# 2021-06-02.net
KiCad netlist of a schematic drawn in Altium Designer
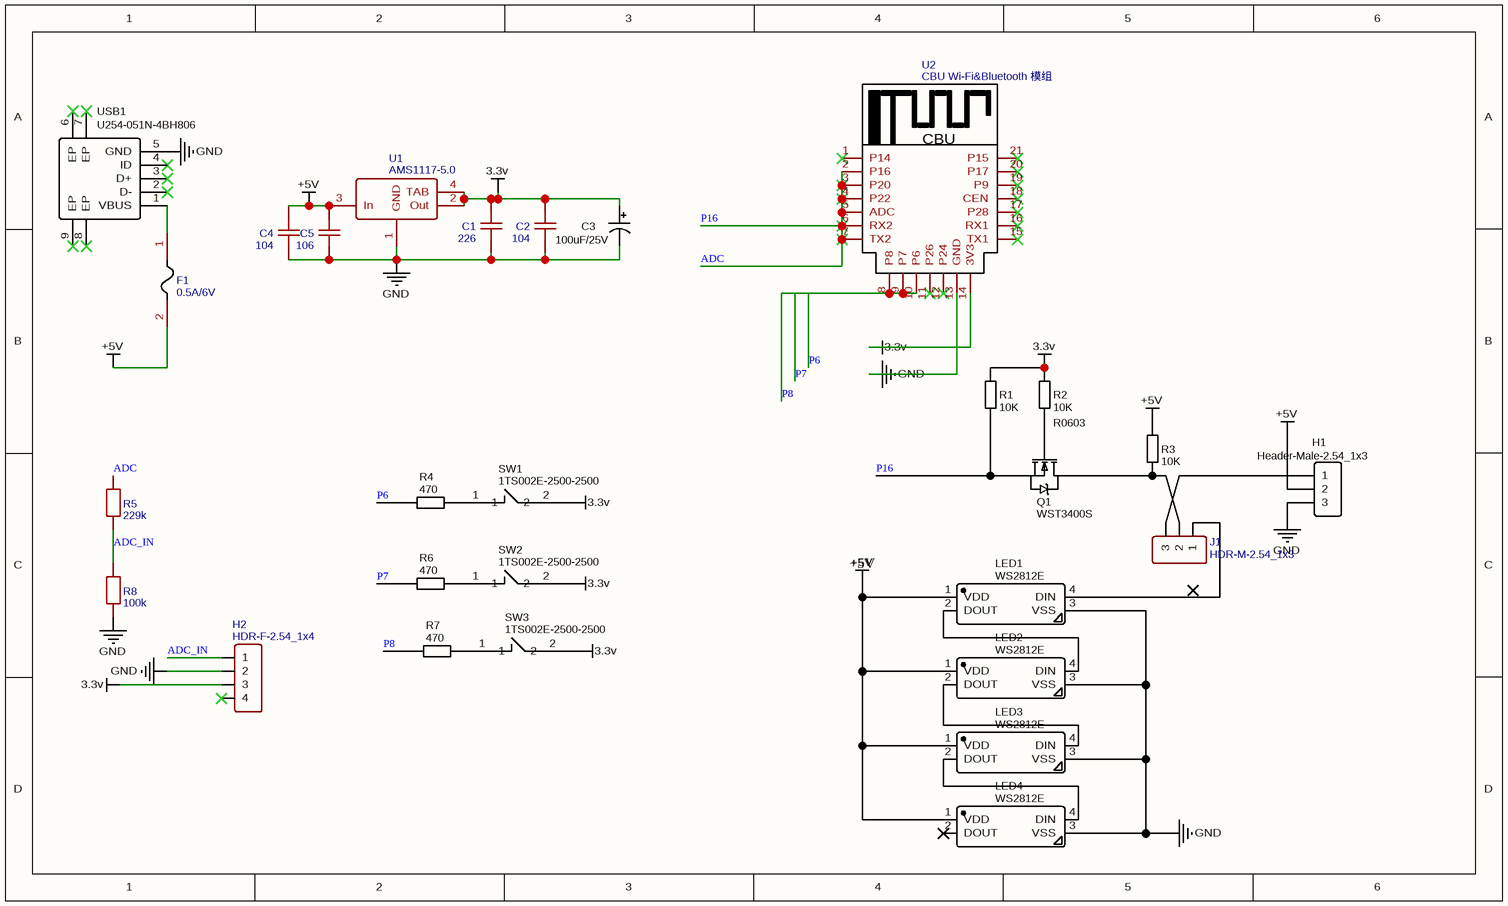
[diagram p0: 原理图_2021-06-02.schdoc]

(export (version "E")
  (design (tool "Eeschema 10.0.6"))
  (components
    (comp (ref "C1")
      (value "226")
      (fields (field (name "BOM_MANUFACTURER PART") "?"))
      (libsource (lib "altium-import") (part "root_1_226_"))
    )
    (comp (ref "C2")
      (value "104")
      (fields (field (name "BOM_MANUFACTURER PART") "?"))
      (libsource (lib "altium-import") (part "root_1_104_"))
    )
    (comp (ref "C3")
      (value "100uF/25V")
      (fields
        (field (name "BOM_MANUFACTURER PART") "RVT1E101M0607")
        (field (name "BOM_SUPPLIER PART") "C3338")
      )
      (libsource (lib "altium-import") (part "root_0_100uF/25V_"))
    )
    (comp (ref "C4")
      (value "104")
      (fields (field (name "BOM_MANUFACTURER PART") "?"))
      (libsource (lib "altium-import") (part "root_1_104_"))
    )
    (comp (ref "C5")
      (value "106")
      (fields (field (name "BOM_MANUFACTURER PART") "?"))
      (libsource (lib "altium-import") (part "root_1_106_"))
    )
    (comp (ref "F1") (value "0.5A/6V") (libsource (lib "altium-import") (part "root_3_0.5A/6V_")))
    (comp (ref "H1")
      (value "Header-Male-2.54_1x3")
      (fields
        (field (name "BOM_MANUFACTURER PART") "Header2.54mm 1*3P")
        (field (name "BOM_SUPPLIER PART") "C49257")
      )
      (libsource (lib "altium-import") (part "root_0_Header-Male-2.54_1x3_"))
    )
    (comp (ref "H2")
      (value "HDR-F-2.54_1x4")
      (fields (field (name "BOM_SUPPLIER PART") "C225501") (field (name "CONTRIBUTOR") "LCEDA_Lib"))
      (libsource (lib "altium-import") (part "root_0_HDR-F-2.54_1x4_"))
    )
    (comp (ref "J1")
      (value "HDR-M-2.54_1x3")
      (fields (field (name "BOM_SUPPLIER PART") "C180248") (field (name "CONTRIBUTOR") "LCEDA_Lib"))
      (libsource (lib "altium-import") (part "root_3_HDR-M-2.54_1x3_"))
    )
    (comp (ref "LED1")
      (value "WS2812E")
      (fields (field (name "BOM_SUPPLIER PART") "C139127") (field (name "CONTRIBUTOR") "LCSC"))
      (libsource (lib "altium-import") (part "root_0_WS2812E_"))
    )
    (comp (ref "LED2")
      (value "WS2812E")
      (fields (field (name "BOM_SUPPLIER PART") "C139127") (field (name "CONTRIBUTOR") "LCSC"))
      (libsource (lib "altium-import") (part "root_0_WS2812E_"))
    )
    (comp (ref "LED3")
      (value "WS2812E")
      (fields (field (name "BOM_SUPPLIER PART") "C139127") (field (name "CONTRIBUTOR") "LCSC"))
      (libsource (lib "altium-import") (part "root_0_WS2812E_"))
    )
    (comp (ref "LED4")
      (value "WS2812E")
      (fields (field (name "BOM_SUPPLIER PART") "C139127") (field (name "CONTRIBUTOR") "LCSC"))
      (libsource (lib "altium-import") (part "root_0_WS2812E_"))
    )
    (comp (ref "Q1")
      (value "WST3400S")
      (fields (field (name "BOM_SUPPLIER PART") "C105164"))
      (libsource (lib "altium-import") (part "root_3_WST3400S_"))
    )
    (comp (ref "R1")
      (value "10K")
      (fields
        (field (name "BOM_MANUFACTURER PART") "RC0603JR-0710KL")
        (field (name "BOM_SUPPLIER PART") "C99198")
      )
      (libsource (lib "altium-import") (part "root_3_10K_"))
    )
    (comp (ref "R2")
      (value "10K")
      (fields
        (field (name "BOM_MANUFACTURER PART") "RC0603JR-0710KL")
        (field (name "BOM_SUPPLIER PART") "C99198")
      )
      (libsource (lib "altium-import") (part "root_3_10K_"))
    )
    (comp (ref "R3")
      (value "10K")
      (fields
        (field (name "BOM_MANUFACTURER PART") "RC0603JR-0710KL")
        (field (name "BOM_SUPPLIER PART") "C99198")
      )
      (libsource (lib "altium-import") (part "root_3_10K_"))
    )
    (comp (ref "R4")
      (value "470")
      (fields
        (field (name "BOM_MANUFACTURER PART") "0603WAJ0471T5E")
        (field (name "BOM_SUPPLIER PART") "C25241")
      )
      (libsource (lib "altium-import") (part "root_2_470_"))
    )
    (comp (ref "R5")
      (value "229k")
      (fields (field (name "CONTRIBUTOR") "LCEDA_Lib"))
      (libsource (lib "altium-import") (part "root_1_229k_"))
    )
    (comp (ref "R6")
      (value "470")
      (fields
        (field (name "BOM_MANUFACTURER PART") "0603WAJ0471T5E")
        (field (name "BOM_SUPPLIER PART") "C25241")
      )
      (libsource (lib "altium-import") (part "root_2_470_"))
    )
    (comp (ref "R7")
      (value "470")
      (fields
        (field (name "BOM_MANUFACTURER PART") "0603WAJ0471T5E")
        (field (name "BOM_SUPPLIER PART") "C25241")
      )
      (libsource (lib "altium-import") (part "root_2_470_"))
    )
    (comp (ref "R8")
      (value "100k")
      (fields (field (name "CONTRIBUTOR") "LCEDA_Lib"))
      (libsource (lib "altium-import") (part "root_1_100k_"))
    )
    (comp (ref "SW1")
      (value "1TS002E-2500-2500")
      (fields (field (name "BOM_SUPPLIER PART") "C329185") (field (name "CONTRIBUTOR") "LCSC"))
      (libsource (lib "altium-import") (part "root_0_1TS002E-2500-2500_"))
    )
    (comp (ref "SW2")
      (value "1TS002E-2500-2500")
      (fields (field (name "BOM_SUPPLIER PART") "C329185") (field (name "CONTRIBUTOR") "LCSC"))
      (libsource (lib "altium-import") (part "root_0_1TS002E-2500-2500_"))
    )
    (comp (ref "SW3")
      (value "1TS002E-2500-2500")
      (fields (field (name "BOM_SUPPLIER PART") "C329185") (field (name "CONTRIBUTOR") "LCSC"))
      (libsource (lib "altium-import") (part "root_0_1TS002E-2500-2500_"))
    )
    (comp (ref "U1")
      (value "AMS1117-5.0")
      (fields (field (name "BOM_SUPPLIER PART") "C6187"))
      (libsource (lib "altium-import") (part "root_0_AMS1117-5.0_"))
    )
    (comp (ref "U2")
      (value "CBU Wi-Fi&Bluetooth 模组")
      (fields (field (name "CONTRIBUTOR") "chenlf"))
      (libsource (lib "altium-import") (part "root_0_CBU Wi-Fi&Bluetooth 模组_"))
    )
    (comp (ref "USB1")
      (value "U254-051N-4BH806")
      (fields (field (name "BOM_SUPPLIER PART") "C319170") (field (name "CONTRIBUTOR") "LCSC"))
      (libsource (lib "altium-import") (part "root_0_U254-051N-4BH806_"))
    )
  )
  (nets
    (net (code "1") (name "+5V") (class "Default")
      (node (ref "C4") (pin "2") (pinfunction "2_2") (pintype "passive"))
      (node (ref "C5") (pin "2") (pinfunction "2_2") (pintype "passive"))
      (node (ref "F1") (pin "2") (pinfunction "2_2") (pintype "passive"))
      (node (ref "H1") (pin "2") (pinfunction "2_2") (pintype "passive"))
      (node (ref "LED1") (pin "1") (pinfunction "VDD_1") (pintype "passive"))
      (node (ref "LED2") (pin "1") (pinfunction "VDD_1") (pintype "passive"))
      (node (ref "LED3") (pin "1") (pinfunction "VDD_1") (pintype "passive"))
      (node (ref "LED4") (pin "1") (pinfunction "VDD_1") (pintype "passive"))
      (node (ref "R3") (pin "1") (pinfunction "1_1") (pintype "passive"))
      (node (ref "U1") (pin "3") (pinfunction "In_3") (pintype "passive"))
    )
    (net (code "2") (name "/ADC") (class "Default")
      (node (ref "Q1") (pin "2") (pinfunction "S_2") (pintype "passive"))
      (node (ref "R1") (pin "2") (pinfunction "2_2") (pintype "passive"))
      (node (ref "R5") (pin "2") (pinfunction "2_2") (pintype "passive"))
      (node (ref "U2") (pin "2") (pinfunction "P16_2") (pintype "passive"))
      (node (ref "U2") (pin "3") (pinfunction "P20_3") (pintype "passive"))
      (node (ref "U2") (pin "4") (pinfunction "P22_4") (pintype "passive"))
      (node (ref "U2") (pin "5") (pinfunction "ADC_5") (pintype "passive"))
      (node (ref "U2") (pin "6") (pinfunction "RX2_6") (pintype "passive"))
      (node (ref "U2") (pin "7") (pinfunction "TX2_7") (pintype "passive"))
    )
    (net (code "3") (name "/ADC_IN") (class "Default")
      (node (ref "H2") (pin "1") (pinfunction "1_1") (pintype "passive"))
      (node (ref "R5") (pin "1") (pinfunction "1_1") (pintype "passive"))
      (node (ref "R8") (pin "2") (pinfunction "2_2") (pintype "passive"))
    )
    (net (code "4") (name "/P6") (class "Default")
      (node (ref "R4") (pin "2") (pinfunction "2_2") (pintype "passive"))
      (node (ref "R6") (pin "2") (pinfunction "2_2") (pintype "passive"))
      (node (ref "R7") (pin "2") (pinfunction "2_2") (pintype "passive"))
      (node (ref "U2") (pin "10") (pinfunction "P6_10") (pintype "passive"))
      (node (ref "U2") (pin "8") (pinfunction "P8_8") (pintype "passive"))
      (node (ref "U2") (pin "9") (pinfunction "P7_9") (pintype "passive"))
    )
    (net (code "5") (name "3.3v") (class "Default")
      (node (ref "C1") (pin "2") (pinfunction "2_2") (pintype "passive"))
      (node (ref "C2") (pin "2") (pinfunction "2_2") (pintype "passive"))
      (node (ref "C3") (pin "1") (pinfunction "1_1") (pintype "passive"))
      (node (ref "H2") (pin "3") (pinfunction "3_3") (pintype "passive"))
      (node (ref "R1") (pin "1") (pinfunction "1_1") (pintype "passive"))
      (node (ref "R2") (pin "1") (pinfunction "1_1") (pintype "passive"))
      (node (ref "SW1") (pin "2") (pinfunction "2_2") (pintype "passive"))
      (node (ref "SW2") (pin "2") (pinfunction "2_2") (pintype "passive"))
      (node (ref "SW3") (pin "2") (pinfunction "2_2") (pintype "passive"))
      (node (ref "U1") (pin "2") (pinfunction "Out_2") (pintype "passive"))
      (node (ref "U1") (pin "4") (pinfunction "TAB_4") (pintype "passive"))
      (node (ref "U2") (pin "14") (pinfunction "3V3_14") (pintype "passive"))
    )
    (net (code "6") (name "GND") (class "Default")
      (node (ref "C1") (pin "1") (pinfunction "1_1") (pintype "passive"))
      (node (ref "C2") (pin "1") (pinfunction "1_1") (pintype "passive"))
      (node (ref "C3") (pin "2") (pinfunction "2_2") (pintype "passive"))
      (node (ref "C4") (pin "1") (pinfunction "1_1") (pintype "passive"))
      (node (ref "C5") (pin "1") (pinfunction "1_1") (pintype "passive"))
      (node (ref "H1") (pin "3") (pinfunction "3_3") (pintype "passive"))
      (node (ref "H2") (pin "2") (pinfunction "2_2") (pintype "passive"))
      (node (ref "LED1") (pin "3") (pinfunction "VSS_3") (pintype "passive"))
      (node (ref "LED2") (pin "3") (pinfunction "VSS_3") (pintype "passive"))
      (node (ref "LED3") (pin "3") (pinfunction "VSS_3") (pintype "passive"))
      (node (ref "LED4") (pin "3") (pinfunction "VSS_3") (pintype "passive"))
      (node (ref "R8") (pin "1") (pinfunction "1_1") (pintype "passive"))
      (node (ref "U1") (pin "1") (pinfunction "GND_1") (pintype "passive"))
      (node (ref "U2") (pin "13") (pinfunction "GND_13") (pintype "passive"))
      (node (ref "USB1") (pin "5") (pinfunction "GND_5") (pintype "passive"))
    )
    (net (code "7") (name "Net-(H1-Pad1)") (class "Default")
      (node (ref "H1") (pin "1") (pinfunction "1_1") (pintype "passive"))
      (node (ref "J1") (pin "3") (pinfunction "3_3") (pintype "passive"))
    )
    (net (code "8") (name "Net-(LED1-DIN)") (class "Default")
      (node (ref "J1") (pin "1") (pinfunction "1_1") (pintype "passive"))
      (node (ref "LED1") (pin "4") (pinfunction "DIN_4") (pintype "passive"))
    )
    (net (code "9") (name "Net-(LED1-DOUT)") (class "Default")
      (node (ref "LED1") (pin "2") (pinfunction "DOUT_2") (pintype "passive"))
      (node (ref "LED2") (pin "4") (pinfunction "DIN_4") (pintype "passive"))
    )
    (net (code "10") (name "Net-(LED2-DOUT)") (class "Default")
      (node (ref "LED2") (pin "2") (pinfunction "DOUT_2") (pintype "passive"))
      (node (ref "LED3") (pin "4") (pinfunction "DIN_4") (pintype "passive"))
    )
    (net (code "11") (name "Net-(LED3-DOUT)") (class "Default")
      (node (ref "LED3") (pin "2") (pinfunction "DOUT_2") (pintype "passive"))
      (node (ref "LED4") (pin "4") (pinfunction "DIN_4") (pintype "passive"))
    )
    (net (code "12") (name "Net-(Q1-D)") (class "Default")
      (node (ref "J1") (pin "2") (pinfunction "2_2") (pintype "passive"))
      (node (ref "Q1") (pin "3") (pinfunction "D_3") (pintype "passive"))
      (node (ref "R3") (pin "2") (pinfunction "2_2") (pintype "passive"))
    )
    (net (code "13") (name "Net-(Q1-G)") (class "Default")
      (node (ref "Q1") (pin "1") (pinfunction "G_1") (pintype "passive"))
      (node (ref "R2") (pin "2") (pinfunction "2_2") (pintype "passive"))
    )
    (net (code "14") (name "Net-(R4-Pad1)") (class "Default")
      (node (ref "R4") (pin "1") (pinfunction "1_1") (pintype "passive"))
      (node (ref "SW1") (pin "1") (pinfunction "1_1") (pintype "passive"))
    )
    (net (code "15") (name "Net-(R6-Pad1)") (class "Default")
      (node (ref "R6") (pin "1") (pinfunction "1_1") (pintype "passive"))
      (node (ref "SW2") (pin "1") (pinfunction "1_1") (pintype "passive"))
    )
    (net (code "16") (name "Net-(R7-Pad1)") (class "Default")
      (node (ref "R7") (pin "1") (pinfunction "1_1") (pintype "passive"))
      (node (ref "SW3") (pin "1") (pinfunction "1_1") (pintype "passive"))
    )
    (net (code "17") (name "Net-(USB1-VBUS)") (class "Default")
      (node (ref "F1") (pin "1") (pinfunction "1_1") (pintype "passive"))
      (node (ref "USB1") (pin "1") (pinfunction "VBUS_1") (pintype "passive"))
    )
    (net (code "18") (name "unconnected-(H2-Pad4)") (class "Default")
      (node (ref "H2") (pin "4") (pinfunction "4_4") (pintype "passive+no_connect"))
    )
    (net (code "19") (name "unconnected-(LED4-DOUT-Pad2)") (class "Default")
      (node (ref "LED4") (pin "2") (pinfunction "DOUT_2") (pintype "passive+no_connect"))
    )
    (net (code "20") (name "unconnected-(U2-CEN-Pad18)") (class "Default")
      (node (ref "U2") (pin "18") (pinfunction "CEN_18") (pintype "passive+no_connect"))
    )
    (net (code "21") (name "unconnected-(U2-P9-Pad19)") (class "Default")
      (node (ref "U2") (pin "19") (pinfunction "P9_19") (pintype "passive+no_connect"))
    )
    (net (code "22") (name "unconnected-(U2-P14-Pad1)") (class "Default")
      (node (ref "U2") (pin "1") (pinfunction "P14_1") (pintype "passive+no_connect"))
    )
    (net (code "23") (name "unconnected-(U2-P15-Pad21)") (class "Default")
      (node (ref "U2") (pin "21") (pinfunction "P15_21") (pintype "passive+no_connect"))
    )
    (net (code "24") (name "unconnected-(U2-P17-Pad20)") (class "Default")
      (node (ref "U2") (pin "20") (pinfunction "P17_20") (pintype "passive+no_connect"))
    )
    (net (code "25") (name "unconnected-(U2-P24-Pad12)") (class "Default")
      (node (ref "U2") (pin "12") (pinfunction "P24_12") (pintype "passive+no_connect"))
    )
    (net (code "26") (name "unconnected-(U2-P26-Pad11)") (class "Default")
      (node (ref "U2") (pin "11") (pinfunction "P26_11") (pintype "passive+no_connect"))
    )
    (net (code "27") (name "unconnected-(U2-P28-Pad17)") (class "Default")
      (node (ref "U2") (pin "17") (pinfunction "P28_17") (pintype "passive+no_connect"))
    )
    (net (code "28") (name "unconnected-(U2-RX1-Pad16)") (class "Default")
      (node (ref "U2") (pin "16") (pinfunction "RX1_16") (pintype "passive+no_connect"))
    )
    (net (code "29") (name "unconnected-(U2-TX1-Pad15)") (class "Default")
      (node (ref "U2") (pin "15") (pinfunction "TX1_15") (pintype "passive+no_connect"))
    )
    (net (code "30") (name "unconnected-(USB1-D+-Pad3)") (class "Default")
      (node (ref "USB1") (pin "3") (pinfunction "D+_3") (pintype "passive+no_connect"))
    )
    (net (code "31") (name "unconnected-(USB1-D--Pad2)") (class "Default")
      (node (ref "USB1") (pin "2") (pinfunction "D-_2") (pintype "passive+no_connect"))
    )
    (net (code "32") (name "unconnected-(USB1-EP-Pad6)") (class "Default")
      (node (ref "USB1") (pin "6") (pinfunction "EP_6") (pintype "passive+no_connect"))
    )
    (net (code "33") (name "unconnected-(USB1-EP-Pad7)") (class "Default")
      (node (ref "USB1") (pin "7") (pinfunction "EP_7") (pintype "passive+no_connect"))
    )
    (net (code "34") (name "unconnected-(USB1-EP-Pad8)") (class "Default")
      (node (ref "USB1") (pin "8") (pinfunction "EP_8") (pintype "passive+no_connect"))
    )
    (net (code "35") (name "unconnected-(USB1-EP-Pad9)") (class "Default")
      (node (ref "USB1") (pin "9") (pinfunction "EP_9") (pintype "passive+no_connect"))
    )
    (net (code "36") (name "unconnected-(USB1-ID-Pad4)") (class "Default")
      (node (ref "USB1") (pin "4") (pinfunction "ID_4") (pintype "passive+no_connect"))
    )
  )
)
